# esp_converter.net
KiCad netlist of a schematic drawn in EAGLE
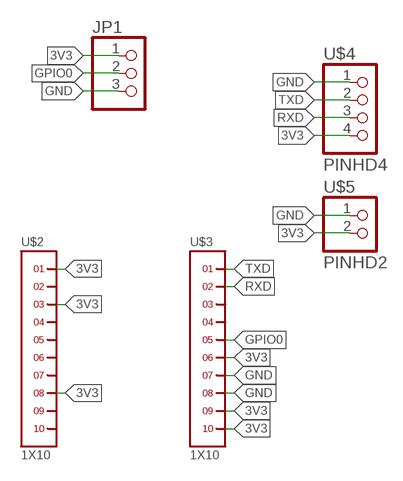
[diagram p0: schematic, sheet 1]

(export (version "E")
  (design (tool "Eeschema 10.0.6"))
  (components
    (comp (ref "JP1")
      (value "PINHD-1X3")
      (footprint "eagle-import:1X03")
      (libsource (lib "eagle-import") (part "PINHD-1X3"))
    )
    (comp (ref "U$2")
      (value "1X10")
      (footprint "eagle-import:1X10")
      (libsource (lib "eagle-import") (part "1X10"))
    )
    (comp (ref "U$3")
      (value "1X10")
      (footprint "eagle-import:1X10")
      (libsource (lib "eagle-import") (part "1X10"))
    )
    (comp (ref "U$4")
      (value "PINHD4")
      (footprint "eagle-import:PINHD4")
      (libsource (lib "eagle-import") (part "PINHD4"))
    )
    (comp (ref "U$5")
      (value "PINHD2")
      (footprint "eagle-import:PINHD2")
      (libsource (lib "eagle-import") (part "PINHD2"))
    )
  )
  (nets
    (net (code "1") (name "3V3") (class "Default")
      (node (ref "JP1") (pin "1") (pinfunction "1_1") (pintype "passive"))
      (node (ref "U$2") (pin "1") (pinfunction "1_1") (pintype "bidirectional"))
      (node (ref "U$2") (pin "3") (pinfunction "3_3") (pintype "bidirectional"))
      (node (ref "U$2") (pin "8") (pinfunction "8_8") (pintype "bidirectional"))
      (node (ref "U$3") (pin "10") (pinfunction "10_10") (pintype "bidirectional"))
      (node (ref "U$3") (pin "6") (pinfunction "6_6") (pintype "bidirectional"))
      (node (ref "U$3") (pin "9") (pinfunction "9_9") (pintype "bidirectional"))
      (node (ref "U$4") (pin "4") (pinfunction "4_4") (pintype "passive"))
      (node (ref "U$5") (pin "2") (pinfunction "2_2") (pintype "passive"))
    )
    (net (code "2") (name "GND") (class "Default")
      (node (ref "JP1") (pin "3") (pinfunction "3_3") (pintype "passive"))
      (node (ref "U$3") (pin "7") (pinfunction "7_7") (pintype "bidirectional"))
      (node (ref "U$3") (pin "8") (pinfunction "8_8") (pintype "bidirectional"))
      (node (ref "U$4") (pin "1") (pinfunction "1_1") (pintype "passive"))
      (node (ref "U$5") (pin "1") (pinfunction "1_1") (pintype "passive"))
    )
    (net (code "3") (name "GPIO0") (class "Default")
      (node (ref "JP1") (pin "2") (pinfunction "2_2") (pintype "passive"))
      (node (ref "U$3") (pin "5") (pinfunction "5_5") (pintype "bidirectional"))
    )
    (net (code "4") (name "RXD") (class "Default")
      (node (ref "U$3") (pin "2") (pinfunction "2_2") (pintype "bidirectional"))
      (node (ref "U$4") (pin "3") (pinfunction "3_3") (pintype "passive"))
    )
    (net (code "5") (name "TXD") (class "Default")
      (node (ref "U$3") (pin "1") (pinfunction "1_1") (pintype "bidirectional"))
      (node (ref "U$4") (pin "2") (pinfunction "2_2") (pintype "passive"))
    )
    (net (code "6") (name "unconnected-(U$2-Pad2)") (class "Default")
      (node (ref "U$2") (pin "2") (pinfunction "2_2") (pintype "bidirectional"))
    )
    (net (code "7") (name "unconnected-(U$2-Pad4)") (class "Default")
      (node (ref "U$2") (pin "4") (pinfunction "4_4") (pintype "bidirectional"))
    )
    (net (code "8") (name "unconnected-(U$2-Pad5)") (class "Default")
      (node (ref "U$2") (pin "5") (pinfunction "5_5") (pintype "bidirectional"))
    )
    (net (code "9") (name "unconnected-(U$2-Pad6)") (class "Default")
      (node (ref "U$2") (pin "6") (pinfunction "6_6") (pintype "bidirectional"))
    )
    (net (code "10") (name "unconnected-(U$2-Pad7)") (class "Default")
      (node (ref "U$2") (pin "7") (pinfunction "7_7") (pintype "bidirectional"))
    )
    (net (code "11") (name "unconnected-(U$2-Pad9)") (class "Default")
      (node (ref "U$2") (pin "9") (pinfunction "9_9") (pintype "bidirectional"))
    )
    (net (code "12") (name "unconnected-(U$2-Pad10)") (class "Default")
      (node (ref "U$2") (pin "10") (pinfunction "10_10") (pintype "bidirectional"))
    )
    (net (code "13") (name "unconnected-(U$3-Pad3)") (class "Default")
      (node (ref "U$3") (pin "3") (pinfunction "3_3") (pintype "bidirectional"))
    )
    (net (code "14") (name "unconnected-(U$3-Pad4)") (class "Default")
      (node (ref "U$3") (pin "4") (pinfunction "4_4") (pintype "bidirectional"))
    )
  )
)
